# receiver_rfm95_5v.net
KiCad netlist of a schematic drawn in EAGLE
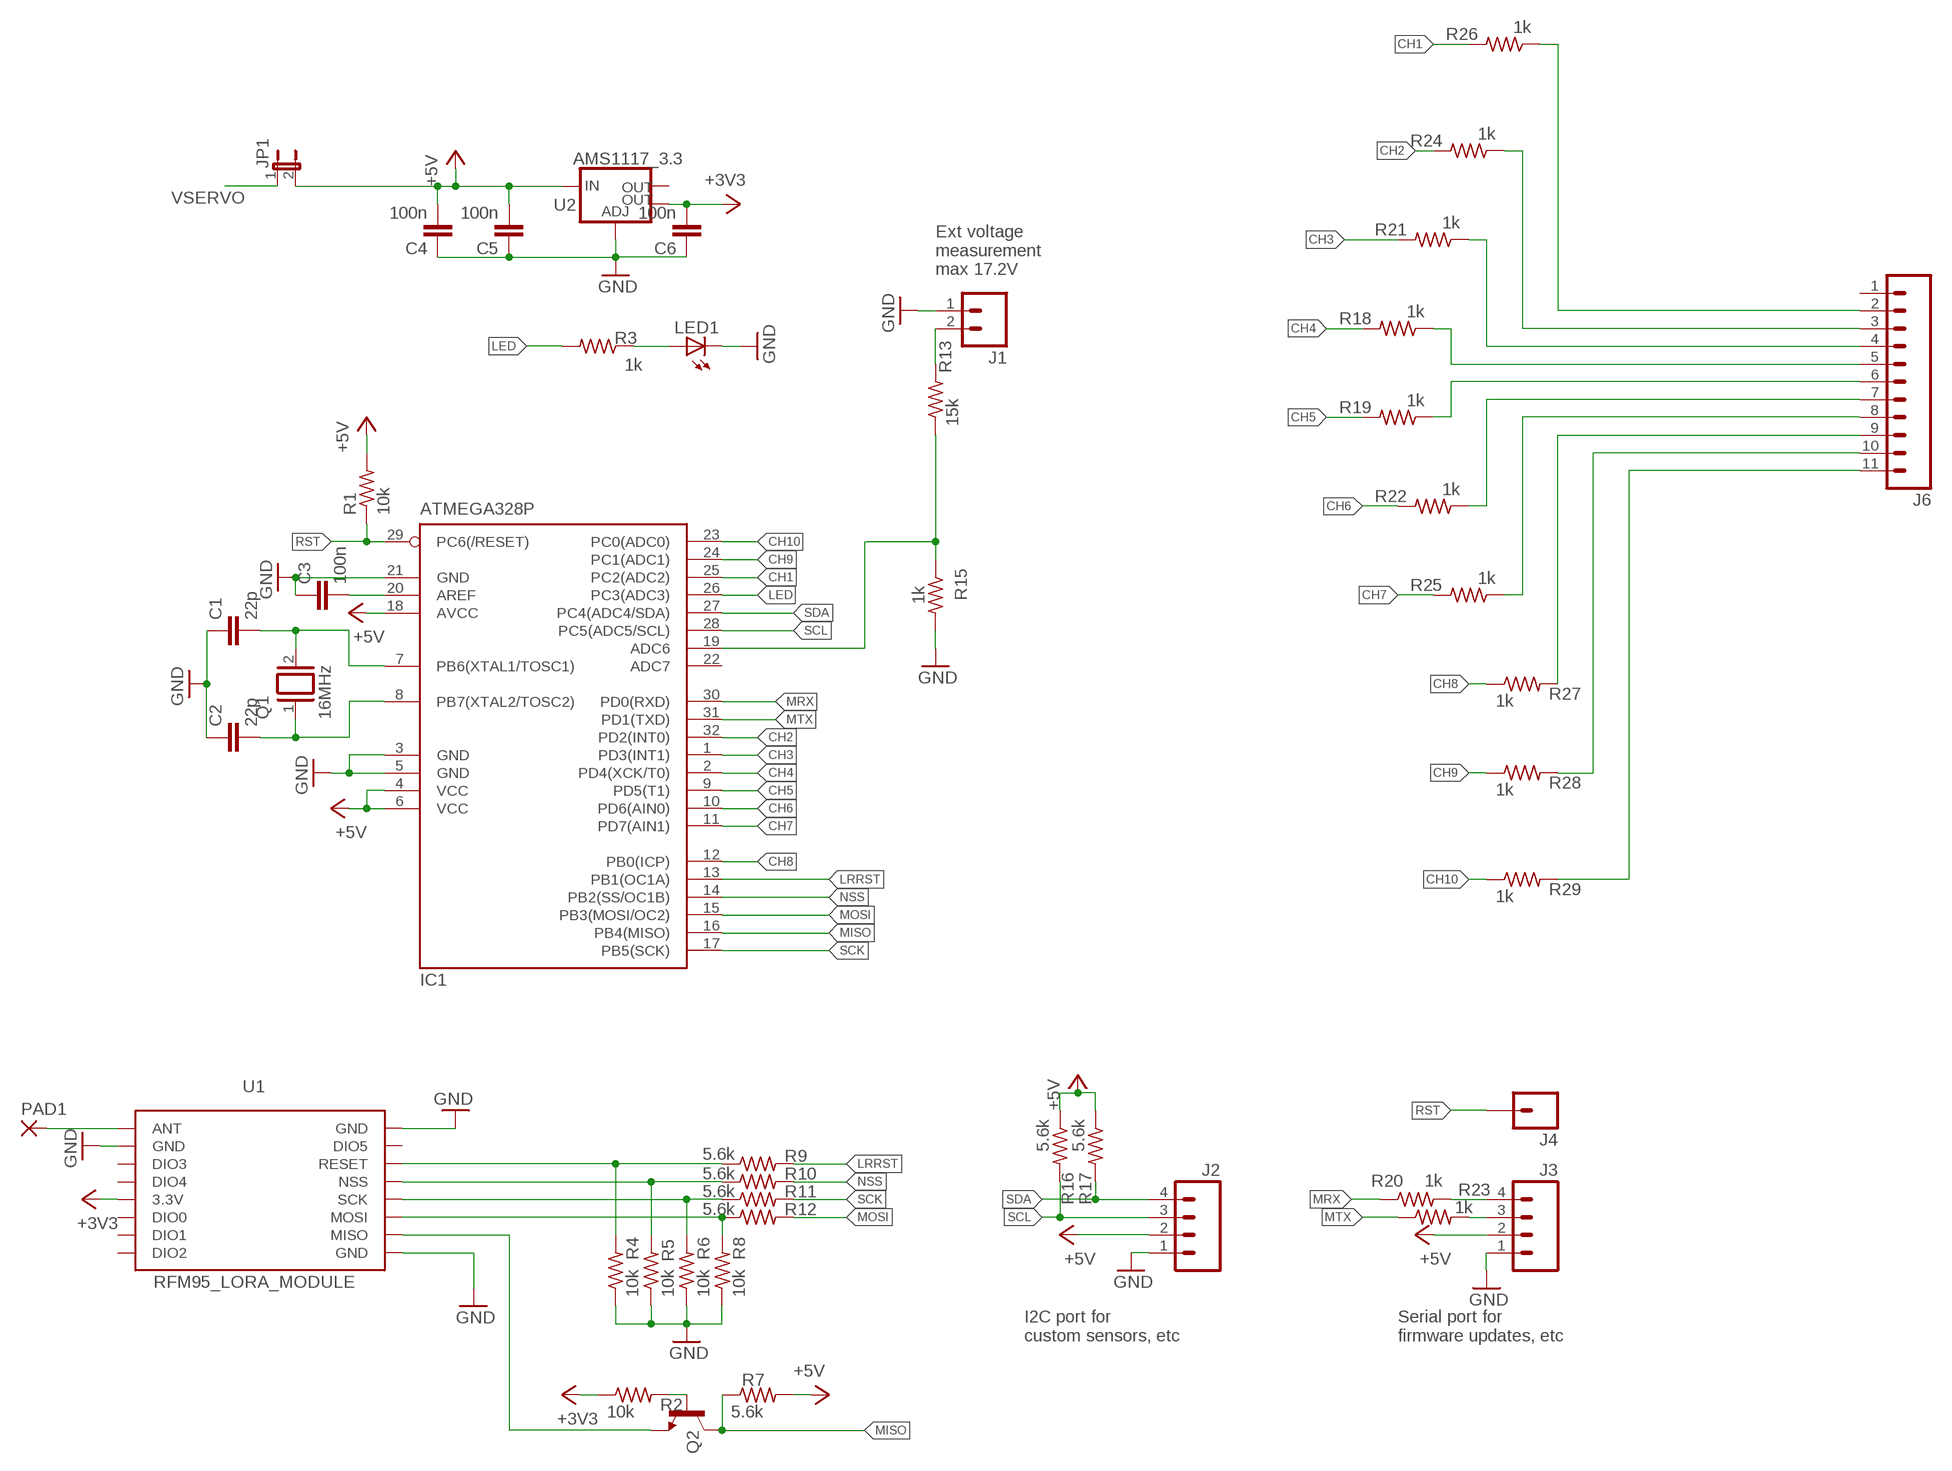
[diagram p0: schematic, sheet 1]

(export (version "E")
  (design (tool "Eeschema 10.0.6"))
  (components
    (comp (ref "C1")
      (value "22p")
      (footprint "eagle-import:C0805K")
      (libsource (lib "eagle-import") (part "C-EUC0805K"))
    )
    (comp (ref "C2")
      (value "22p")
      (footprint "eagle-import:C0805K")
      (libsource (lib "eagle-import") (part "C-EUC0805K"))
    )
    (comp (ref "C3")
      (value "100n")
      (footprint "eagle-import:C0805K")
      (libsource (lib "eagle-import") (part "C-EUC0805K"))
    )
    (comp (ref "C4")
      (value "100n")
      (footprint "eagle-import:C0805K")
      (libsource (lib "eagle-import") (part "C-EUC0805K"))
    )
    (comp (ref "C5")
      (value "100n")
      (footprint "eagle-import:C0805K")
      (libsource (lib "eagle-import") (part "C-EUC0805K"))
    )
    (comp (ref "C6")
      (value "100n")
      (footprint "eagle-import:C0805K")
      (libsource (lib "eagle-import") (part "C-EUC0805K"))
    )
    (comp (ref "IC1")
      (value "ATMEGA328P")
      (footprint "eagle-import:TQFP32-08")
      (fields (field (name "MPN") "ATMEGA8-16AU"))
      (libsource (lib "eagle-import") (part "MEGA8-AI"))
    )
    (comp (ref "J1")
      (value "M02PTH")
      (footprint "eagle-import:1X02")
      (libsource (lib "eagle-import") (part "M02PTH"))
    )
    (comp (ref "J2")
      (value "M04PTH")
      (footprint "eagle-import:1X04")
      (libsource (lib "eagle-import") (part "M04PTH"))
    )
    (comp (ref "J3")
      (value "M04PTH")
      (footprint "eagle-import:1X04")
      (libsource (lib "eagle-import") (part "M04PTH"))
    )
    (comp (ref "J4")
      (value "M01PTH")
      (footprint "eagle-import:1X01")
      (libsource (lib "eagle-import") (part "M01PTH"))
    )
    (comp (ref "J6")
      (value "M11PTH")
      (footprint "eagle-import:1X11")
      (libsource (lib "eagle-import") (part "M11PTH"))
    )
    (comp (ref "JP1")
      (value "JP1E")
      (footprint "eagle-import:JP1")
      (libsource (lib "eagle-import") (part "JP1E"))
    )
    (comp (ref "LED1")
      (value "LEDCHIPLED_1206")
      (footprint "eagle-import:CHIPLED_1206")
      (libsource (lib "eagle-import") (part "LEDCHIPLED_1206"))
    )
    (comp (ref "PAD1")
      (value "2,15/1,0")
      (footprint "eagle-import:2,15_1,0")
      (libsource (lib "eagle-import") (part "2,15/1,0"))
    )
    (comp (ref "Q1")
      (value "16MHz")
      (footprint "eagle-import:QS")
      (libsource (lib "eagle-import") (part "XTAL/S"))
    )
    (comp (ref "Q2")
      (value "BC817-16SMD")
      (footprint "eagle-import:SOT23-BEC")
      (libsource (lib "eagle-import") (part "BC817SMD-16"))
    )
    (comp (ref "R1")
      (value "10k")
      (footprint "eagle-import:R0805")
      (libsource (lib "eagle-import") (part "R-US_R0805"))
    )
    (comp (ref "R2")
      (value "10k")
      (footprint "eagle-import:R0805")
      (libsource (lib "eagle-import") (part "R-US_R0805"))
    )
    (comp (ref "R3")
      (value "1k")
      (footprint "eagle-import:R0805")
      (libsource (lib "eagle-import") (part "R-US_R0805"))
    )
    (comp (ref "R4")
      (value "10k")
      (footprint "eagle-import:R0805")
      (libsource (lib "eagle-import") (part "R-US_R0805"))
    )
    (comp (ref "R5")
      (value "10k")
      (footprint "eagle-import:R0805")
      (libsource (lib "eagle-import") (part "R-US_R0805"))
    )
    (comp (ref "R6")
      (value "10k")
      (footprint "eagle-import:R0805")
      (libsource (lib "eagle-import") (part "R-US_R0805"))
    )
    (comp (ref "R7")
      (value "5.6k")
      (footprint "eagle-import:R0805")
      (libsource (lib "eagle-import") (part "R-US_R0805"))
    )
    (comp (ref "R8")
      (value "10k")
      (footprint "eagle-import:R0805")
      (libsource (lib "eagle-import") (part "R-US_R0805"))
    )
    (comp (ref "R9")
      (value "5.6k")
      (footprint "eagle-import:R0805")
      (libsource (lib "eagle-import") (part "R-US_R0805"))
    )
    (comp (ref "R10")
      (value "5.6k")
      (footprint "eagle-import:R0805")
      (libsource (lib "eagle-import") (part "R-US_R0805"))
    )
    (comp (ref "R11")
      (value "5.6k")
      (footprint "eagle-import:R0805")
      (libsource (lib "eagle-import") (part "R-US_R0805"))
    )
    (comp (ref "R12")
      (value "5.6k")
      (footprint "eagle-import:R0805")
      (libsource (lib "eagle-import") (part "R-US_R0805"))
    )
    (comp (ref "R13")
      (value "15k")
      (footprint "eagle-import:R0805")
      (libsource (lib "eagle-import") (part "R-US_R0805"))
    )
    (comp (ref "R15")
      (value "1k")
      (footprint "eagle-import:R0805")
      (libsource (lib "eagle-import") (part "R-US_R0805"))
    )
    (comp (ref "R16")
      (value "5.6k")
      (footprint "eagle-import:R0805")
      (libsource (lib "eagle-import") (part "R-US_R0805"))
    )
    (comp (ref "R17")
      (value "5.6k")
      (footprint "eagle-import:R0805")
      (libsource (lib "eagle-import") (part "R-US_R0805"))
    )
    (comp (ref "R18")
      (value "1k")
      (footprint "eagle-import:R0805")
      (libsource (lib "eagle-import") (part "R-US_R0805"))
    )
    (comp (ref "R19")
      (value "1k")
      (footprint "eagle-import:R0805")
      (libsource (lib "eagle-import") (part "R-US_R0805"))
    )
    (comp (ref "R20")
      (value "1k")
      (footprint "eagle-import:R0805")
      (libsource (lib "eagle-import") (part "R-US_R0805"))
    )
    (comp (ref "R21")
      (value "1k")
      (footprint "eagle-import:R0805")
      (libsource (lib "eagle-import") (part "R-US_R0805"))
    )
    (comp (ref "R22")
      (value "1k")
      (footprint "eagle-import:R0805")
      (libsource (lib "eagle-import") (part "R-US_R0805"))
    )
    (comp (ref "R23")
      (value "1k")
      (footprint "eagle-import:R0805")
      (libsource (lib "eagle-import") (part "R-US_R0805"))
    )
    (comp (ref "R24")
      (value "1k")
      (footprint "eagle-import:R0805")
      (libsource (lib "eagle-import") (part "R-US_R0805"))
    )
    (comp (ref "R25")
      (value "1k")
      (footprint "eagle-import:R0805")
      (libsource (lib "eagle-import") (part "R-US_R0805"))
    )
    (comp (ref "R26")
      (value "1k")
      (footprint "eagle-import:R0805")
      (libsource (lib "eagle-import") (part "R-US_R0805"))
    )
    (comp (ref "R27")
      (value "1k")
      (footprint "eagle-import:R0805")
      (libsource (lib "eagle-import") (part "R-US_R0805"))
    )
    (comp (ref "R28")
      (value "1k")
      (footprint "eagle-import:R0805")
      (libsource (lib "eagle-import") (part "R-US_R0805"))
    )
    (comp (ref "R29")
      (value "1k")
      (footprint "eagle-import:R0805")
      (libsource (lib "eagle-import") (part "R-US_R0805"))
    )
    (comp (ref "U1")
      (value "RFM95_LORA_MODULE")
      (footprint "eagle-import:RFM95")
      (libsource (lib "eagle-import") (part "RFM95_LORA_MODULE"))
    )
    (comp (ref "U2")
      (value "AMS1117_3.3")
      (footprint "eagle-import:SOT223")
      (libsource (lib "eagle-import") (part "V_REG_LM1117SOT223"))
    )
  )
  (nets
    (net (code "1") (name "+3V3") (class "Default")
      (node (ref "C6") (pin "2") (pinfunction "2_2") (pintype "passive"))
      (node (ref "R2") (pin "1") (pinfunction "1_1") (pintype "passive"))
      (node (ref "U1") (pin "3.3V") (pinfunction "3.3V_3.3V") (pintype "bidirectional"))
      (node (ref "U2") (pin "4") (pinfunction "OUT_4") (pintype "output"))
    )
    (net (code "2") (name "+5V") (class "Default")
      (node (ref "C4") (pin "2") (pinfunction "2_2") (pintype "passive"))
      (node (ref "C5") (pin "2") (pinfunction "2_2") (pintype "passive"))
      (node (ref "IC1") (pin "18") (pinfunction "AVCC_18") (pintype "power_in"))
      (node (ref "IC1") (pin "4") (pinfunction "VCC_4") (pintype "power_in"))
      (node (ref "IC1") (pin "6") (pinfunction "VCC_6") (pintype "power_in"))
      (node (ref "J2") (pin "2") (pinfunction "2_2") (pintype "passive"))
      (node (ref "J3") (pin "2") (pinfunction "2_2") (pintype "passive"))
      (node (ref "JP1") (pin "2") (pinfunction "2_2") (pintype "passive"))
      (node (ref "R1") (pin "2") (pinfunction "2_2") (pintype "passive"))
      (node (ref "R16") (pin "1") (pinfunction "1_1") (pintype "passive"))
      (node (ref "R17") (pin "1") (pinfunction "1_1") (pintype "passive"))
      (node (ref "R7") (pin "2") (pinfunction "2_2") (pintype "passive"))
      (node (ref "U2") (pin "3") (pinfunction "IN_3") (pintype "input"))
    )
    (net (code "3") (name "/DIO3") (class "Default")
      (node (ref "U1") (pin "DIO3") (pinfunction "DIO3_DIO3") (pintype "power_in"))
    )
    (net (code "4") (name "/VSERVO") (class "Default")
      (node (ref "JP1") (pin "1") (pinfunction "1_1") (pintype "passive"))
    )
    (net (code "5") (name "CH1") (class "Default")
      (node (ref "IC1") (pin "25") (pinfunction "PC2(ADC2)_25") (pintype "bidirectional"))
      (node (ref "R26") (pin "2") (pinfunction "2_2") (pintype "passive"))
    )
    (net (code "6") (name "CH2") (class "Default")
      (node (ref "IC1") (pin "32") (pinfunction "PD2(INT0)_32") (pintype "bidirectional"))
      (node (ref "R24") (pin "2") (pinfunction "2_2") (pintype "passive"))
    )
    (net (code "7") (name "CH3") (class "Default")
      (node (ref "IC1") (pin "1") (pinfunction "PD3(INT1)_1") (pintype "bidirectional"))
      (node (ref "R21") (pin "2") (pinfunction "2_2") (pintype "passive"))
    )
    (net (code "8") (name "CH4") (class "Default")
      (node (ref "IC1") (pin "2") (pinfunction "PD4(XCK/T0)_2") (pintype "bidirectional"))
      (node (ref "R18") (pin "2") (pinfunction "2_2") (pintype "passive"))
    )
    (net (code "9") (name "CH5") (class "Default")
      (node (ref "IC1") (pin "9") (pinfunction "PD5(T1)_9") (pintype "bidirectional"))
      (node (ref "R19") (pin "2") (pinfunction "2_2") (pintype "passive"))
    )
    (net (code "10") (name "CH6") (class "Default")
      (node (ref "IC1") (pin "10") (pinfunction "PD6(AIN0)_10") (pintype "bidirectional"))
      (node (ref "R22") (pin "2") (pinfunction "2_2") (pintype "passive"))
    )
    (net (code "11") (name "CH7") (class "Default")
      (node (ref "IC1") (pin "11") (pinfunction "PD7(AIN1)_11") (pintype "bidirectional"))
      (node (ref "R25") (pin "2") (pinfunction "2_2") (pintype "passive"))
    )
    (net (code "12") (name "CH8") (class "Default")
      (node (ref "IC1") (pin "12") (pinfunction "PB0(ICP)_12") (pintype "bidirectional"))
      (node (ref "R27") (pin "1") (pinfunction "1_1") (pintype "passive"))
    )
    (net (code "13") (name "CH9") (class "Default")
      (node (ref "IC1") (pin "24") (pinfunction "PC1(ADC1)_24") (pintype "bidirectional"))
      (node (ref "R28") (pin "1") (pinfunction "1_1") (pintype "passive"))
    )
    (net (code "14") (name "CH10") (class "Default")
      (node (ref "IC1") (pin "23") (pinfunction "PC0(ADC0)_23") (pintype "bidirectional"))
      (node (ref "R29") (pin "1") (pinfunction "1_1") (pintype "passive"))
    )
    (net (code "15") (name "GND") (class "Default")
      (node (ref "C1") (pin "1") (pinfunction "1_1") (pintype "passive"))
      (node (ref "C2") (pin "1") (pinfunction "1_1") (pintype "passive"))
      (node (ref "C3") (pin "1") (pinfunction "1_1") (pintype "passive"))
      (node (ref "C4") (pin "1") (pinfunction "1_1") (pintype "passive"))
      (node (ref "C5") (pin "1") (pinfunction "1_1") (pintype "passive"))
      (node (ref "C6") (pin "1") (pinfunction "1_1") (pintype "passive"))
      (node (ref "IC1") (pin "21") (pinfunction "GND_21") (pintype "power_in"))
      (node (ref "IC1") (pin "3") (pinfunction "GND_3") (pintype "power_in"))
      (node (ref "IC1") (pin "5") (pinfunction "GND_5") (pintype "power_in"))
      (node (ref "J1") (pin "1") (pinfunction "1_1") (pintype "passive"))
      (node (ref "J2") (pin "1") (pinfunction "1_1") (pintype "passive"))
      (node (ref "J3") (pin "1") (pinfunction "1_1") (pintype "passive"))
      (node (ref "LED1") (pin "C") (pinfunction "C_C") (pintype "passive"))
      (node (ref "R15") (pin "2") (pinfunction "2_2") (pintype "passive"))
      (node (ref "R4") (pin "1") (pinfunction "1_1") (pintype "passive"))
      (node (ref "R5") (pin "1") (pinfunction "1_1") (pintype "passive"))
      (node (ref "R6") (pin "1") (pinfunction "1_1") (pintype "passive"))
      (node (ref "R8") (pin "1") (pinfunction "1_1") (pintype "passive"))
      (node (ref "U1") (pin "GND") (pinfunction "GND_GND") (pintype "power_in"))
      (node (ref "U1") (pin "GND@1") (pinfunction "GND_GND@1") (pintype "power_in"))
      (node (ref "U1") (pin "GND@2") (pinfunction "GND_GND@2") (pintype "power_in"))
      (node (ref "U2") (pin "1") (pinfunction "ADJ_1") (pintype "input"))
    )
    (net (code "16") (name "LED") (class "Default")
      (node (ref "IC1") (pin "26") (pinfunction "PC3(ADC3)_26") (pintype "bidirectional"))
      (node (ref "R3") (pin "2") (pinfunction "2_2") (pintype "passive"))
    )
    (net (code "17") (name "LRRST") (class "Default")
      (node (ref "IC1") (pin "13") (pinfunction "PB1(OC1A)_13") (pintype "bidirectional"))
      (node (ref "R9") (pin "2") (pinfunction "2_2") (pintype "passive"))
    )
    (net (code "18") (name "MISO") (class "Default")
      (node (ref "IC1") (pin "16") (pinfunction "PB4(MISO)_16") (pintype "bidirectional"))
      (node (ref "Q2") (pin "C") (pinfunction "C_C") (pintype "passive"))
      (node (ref "R7") (pin "1") (pinfunction "1_1") (pintype "passive"))
    )
    (net (code "19") (name "MOSI") (class "Default")
      (node (ref "IC1") (pin "15") (pinfunction "PB3(MOSI/OC2)_15") (pintype "bidirectional"))
      (node (ref "R12") (pin "2") (pinfunction "2_2") (pintype "passive"))
    )
    (net (code "20") (name "MRX") (class "Default")
      (node (ref "IC1") (pin "30") (pinfunction "PD0(RXD)_30") (pintype "bidirectional"))
      (node (ref "R20") (pin "1") (pinfunction "1_1") (pintype "passive"))
    )
    (net (code "21") (name "MTX") (class "Default")
      (node (ref "IC1") (pin "31") (pinfunction "PD1(TXD)_31") (pintype "bidirectional"))
      (node (ref "R23") (pin "1") (pinfunction "1_1") (pintype "passive"))
    )
    (net (code "22") (name "NSS") (class "Default")
      (node (ref "IC1") (pin "14") (pinfunction "PB2(SS/OC1B)_14") (pintype "bidirectional"))
      (node (ref "R10") (pin "2") (pinfunction "2_2") (pintype "passive"))
    )
    (net (code "23") (name "Net-(IC1-ADC6)") (class "Default")
      (node (ref "IC1") (pin "19") (pinfunction "ADC6_19") (pintype "bidirectional"))
      (node (ref "R13") (pin "1") (pinfunction "1_1") (pintype "passive"))
      (node (ref "R15") (pin "1") (pinfunction "1_1") (pintype "passive"))
    )
    (net (code "24") (name "Net-(IC1-AREF)") (class "Default")
      (node (ref "C3") (pin "2") (pinfunction "2_2") (pintype "passive"))
      (node (ref "IC1") (pin "20") (pinfunction "AREF_20") (pintype "passive"))
    )
    (net (code "25") (name "Net-(IC1-PB6(XTAL1{slash}TOSC1))") (class "Default")
      (node (ref "C1") (pin "2") (pinfunction "2_2") (pintype "passive"))
      (node (ref "IC1") (pin "7") (pinfunction "PB6(XTAL1/TOSC1)_7") (pintype "bidirectional"))
      (node (ref "Q1") (pin "2") (pinfunction "2_2") (pintype "passive"))
    )
    (net (code "26") (name "Net-(IC1-PB7(XTAL2{slash}TOSC2))") (class "Default")
      (node (ref "C2") (pin "2") (pinfunction "2_2") (pintype "passive"))
      (node (ref "IC1") (pin "8") (pinfunction "PB7(XTAL2/TOSC2)_8") (pintype "bidirectional"))
      (node (ref "Q1") (pin "1") (pinfunction "1_1") (pintype "passive"))
    )
    (net (code "27") (name "Net-(J1-Pad2)") (class "Default")
      (node (ref "J1") (pin "2") (pinfunction "2_2") (pintype "passive"))
      (node (ref "R13") (pin "2") (pinfunction "2_2") (pintype "passive"))
    )
    (net (code "28") (name "Net-(J3-Pad3)") (class "Default")
      (node (ref "J3") (pin "3") (pinfunction "3_3") (pintype "passive"))
      (node (ref "R23") (pin "2") (pinfunction "2_2") (pintype "passive"))
    )
    (net (code "29") (name "Net-(J3-Pad4)") (class "Default")
      (node (ref "J3") (pin "4") (pinfunction "4_4") (pintype "passive"))
      (node (ref "R20") (pin "2") (pinfunction "2_2") (pintype "passive"))
    )
    (net (code "30") (name "Net-(J6-Pad2)") (class "Default")
      (node (ref "J6") (pin "2") (pinfunction "2_2") (pintype "passive"))
      (node (ref "R26") (pin "1") (pinfunction "1_1") (pintype "passive"))
    )
    (net (code "31") (name "Net-(J6-Pad3)") (class "Default")
      (node (ref "J6") (pin "3") (pinfunction "3_3") (pintype "passive"))
      (node (ref "R24") (pin "1") (pinfunction "1_1") (pintype "passive"))
    )
    (net (code "32") (name "Net-(J6-Pad4)") (class "Default")
      (node (ref "J6") (pin "4") (pinfunction "4_4") (pintype "passive"))
      (node (ref "R21") (pin "1") (pinfunction "1_1") (pintype "passive"))
    )
    (net (code "33") (name "Net-(J6-Pad5)") (class "Default")
      (node (ref "J6") (pin "5") (pinfunction "5_5") (pintype "passive"))
      (node (ref "R18") (pin "1") (pinfunction "1_1") (pintype "passive"))
    )
    (net (code "34") (name "Net-(J6-Pad6)") (class "Default")
      (node (ref "J6") (pin "6") (pinfunction "6_6") (pintype "passive"))
      (node (ref "R19") (pin "1") (pinfunction "1_1") (pintype "passive"))
    )
    (net (code "35") (name "Net-(J6-Pad7)") (class "Default")
      (node (ref "J6") (pin "7") (pinfunction "7_7") (pintype "passive"))
      (node (ref "R22") (pin "1") (pinfunction "1_1") (pintype "passive"))
    )
    (net (code "36") (name "Net-(J6-Pad8)") (class "Default")
      (node (ref "J6") (pin "8") (pinfunction "8_8") (pintype "passive"))
      (node (ref "R25") (pin "1") (pinfunction "1_1") (pintype "passive"))
    )
    (net (code "37") (name "Net-(J6-Pad9)") (class "Default")
      (node (ref "J6") (pin "9") (pinfunction "9_9") (pintype "passive"))
      (node (ref "R27") (pin "2") (pinfunction "2_2") (pintype "passive"))
    )
    (net (code "38") (name "Net-(J6-Pad10)") (class "Default")
      (node (ref "J6") (pin "10") (pinfunction "10_10") (pintype "passive"))
      (node (ref "R28") (pin "2") (pinfunction "2_2") (pintype "passive"))
    )
    (net (code "39") (name "Net-(J6-Pad11)") (class "Default")
      (node (ref "J6") (pin "11") (pinfunction "11_11") (pintype "passive"))
      (node (ref "R29") (pin "2") (pinfunction "2_2") (pintype "passive"))
    )
    (net (code "40") (name "Net-(LED1-PadA)") (class "Default")
      (node (ref "LED1") (pin "A") (pinfunction "A_A") (pintype "passive"))
      (node (ref "R3") (pin "1") (pinfunction "1_1") (pintype "passive"))
    )
    (net (code "41") (name "Net-(PAD1-P)") (class "Default")
      (node (ref "PAD1") (pin "1") (pinfunction "P_1") (pintype "passive"))
      (node (ref "U1") (pin "ANT") (pinfunction "ANT_ANT") (pintype "power_in"))
    )
    (net (code "42") (name "Net-(Q2-PadB)") (class "Default")
      (node (ref "Q2") (pin "B") (pinfunction "B_B") (pintype "passive"))
      (node (ref "R2") (pin "2") (pinfunction "2_2") (pintype "passive"))
    )
    (net (code "43") (name "Net-(Q2-PadE)") (class "Default")
      (node (ref "Q2") (pin "E") (pinfunction "E_E") (pintype "passive"))
      (node (ref "U1") (pin "MISO") (pinfunction "MISO_MISO") (pintype "bidirectional"))
    )
    (net (code "44") (name "Net-(R4-Pad2)") (class "Default")
      (node (ref "R4") (pin "2") (pinfunction "2_2") (pintype "passive"))
      (node (ref "R9") (pin "1") (pinfunction "1_1") (pintype "passive"))
      (node (ref "U1") (pin "RESET") (pinfunction "RESET_RESET") (pintype "bidirectional"))
    )
    (net (code "45") (name "Net-(R10-Pad1)") (class "Default")
      (node (ref "R10") (pin "1") (pinfunction "1_1") (pintype "passive"))
      (node (ref "R5") (pin "2") (pinfunction "2_2") (pintype "passive"))
      (node (ref "U1") (pin "NSS") (pinfunction "NSS_NSS") (pintype "bidirectional"))
    )
    (net (code "46") (name "Net-(R11-Pad1)") (class "Default")
      (node (ref "R11") (pin "1") (pinfunction "1_1") (pintype "passive"))
      (node (ref "R6") (pin "2") (pinfunction "2_2") (pintype "passive"))
      (node (ref "U1") (pin "SCK") (pinfunction "SCK_SCK") (pintype "bidirectional"))
    )
    (net (code "47") (name "Net-(R12-Pad1)") (class "Default")
      (node (ref "R12") (pin "1") (pinfunction "1_1") (pintype "passive"))
      (node (ref "R8") (pin "2") (pinfunction "2_2") (pintype "passive"))
      (node (ref "U1") (pin "MOSI") (pinfunction "MOSI_MOSI") (pintype "bidirectional"))
    )
    (net (code "48") (name "RST") (class "Default")
      (node (ref "IC1") (pin "29") (pinfunction "PC6(/RESET)_29") (pintype "bidirectional"))
      (node (ref "J4") (pin "1") (pinfunction "1_1") (pintype "passive"))
      (node (ref "R1") (pin "1") (pinfunction "1_1") (pintype "passive"))
    )
    (net (code "49") (name "SCK") (class "Default")
      (node (ref "IC1") (pin "17") (pinfunction "PB5(SCK)_17") (pintype "bidirectional"))
      (node (ref "R11") (pin "2") (pinfunction "2_2") (pintype "passive"))
    )
    (net (code "50") (name "SCL") (class "Default")
      (node (ref "IC1") (pin "28") (pinfunction "PC5(ADC5/SCL)_28") (pintype "bidirectional"))
      (node (ref "J2") (pin "3") (pinfunction "3_3") (pintype "passive"))
      (node (ref "R16") (pin "2") (pinfunction "2_2") (pintype "passive"))
    )
    (net (code "51") (name "SDA") (class "Default")
      (node (ref "IC1") (pin "27") (pinfunction "PC4(ADC4/SDA)_27") (pintype "bidirectional"))
      (node (ref "J2") (pin "4") (pinfunction "4_4") (pintype "passive"))
      (node (ref "R17") (pin "2") (pinfunction "2_2") (pintype "passive"))
    )
    (net (code "52") (name "unconnected-(IC1-ADC7-Pad22)") (class "Default")
      (node (ref "IC1") (pin "22") (pinfunction "ADC7_22") (pintype "bidirectional"))
    )
    (net (code "53") (name "unconnected-(J6-Pad1)") (class "Default")
      (node (ref "J6") (pin "1") (pinfunction "1_1") (pintype "passive"))
    )
    (net (code "54") (name "unconnected-(U1-PadDIO0)") (class "Default")
      (node (ref "U1") (pin "DIO0") (pinfunction "DIO0_DIO0") (pintype "bidirectional"))
    )
    (net (code "55") (name "unconnected-(U1-PadDIO1)") (class "Default")
      (node (ref "U1") (pin "DIO1") (pinfunction "DIO1_DIO1") (pintype "bidirectional"))
    )
    (net (code "56") (name "unconnected-(U1-PadDIO2)") (class "Default")
      (node (ref "U1") (pin "DIO2") (pinfunction "DIO2_DIO2") (pintype "bidirectional"))
    )
    (net (code "57") (name "unconnected-(U1-PadDIO4)") (class "Default")
      (node (ref "U1") (pin "DIO4") (pinfunction "DIO4_DIO4") (pintype "bidirectional"))
    )
    (net (code "58") (name "unconnected-(U1-PadDIO5)") (class "Default")
      (node (ref "U1") (pin "DIO5") (pinfunction "DIO5_DIO5") (pintype "bidirectional"))
    )
    (net (code "59") (name "unconnected-(U2-OUT-Pad2)") (class "Default")
      (node (ref "U2") (pin "2") (pinfunction "OUT_2") (pintype "output"))
    )
  )
)
